# Motor.net
KiCad netlist of a schematic drawn in Altium Designer
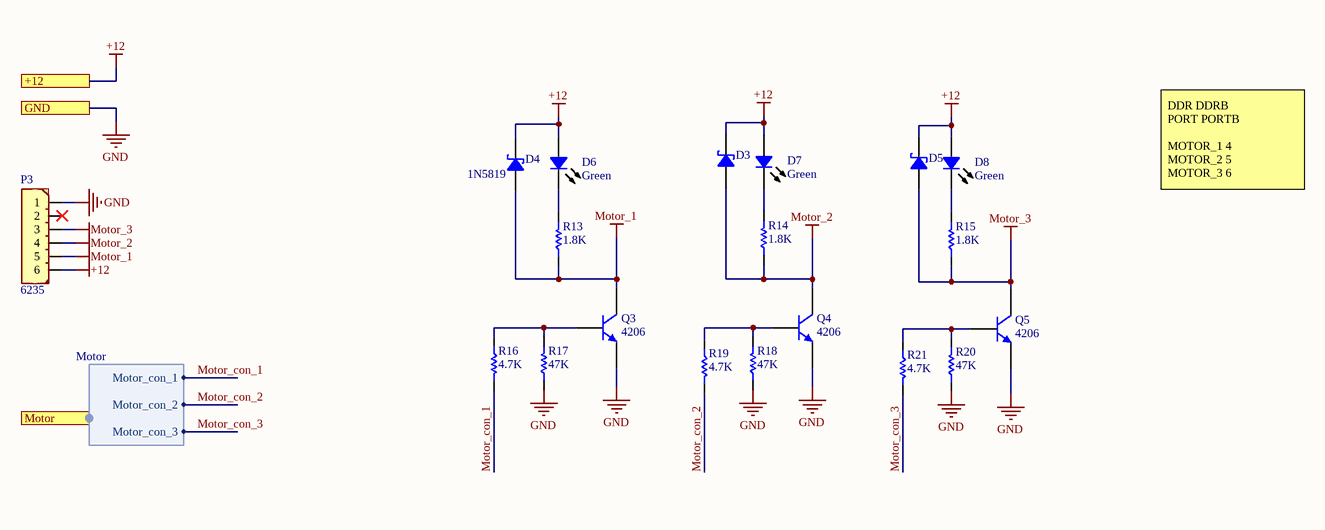
[diagram p0: Motor.SchDoc]

(export (version "E")
  (design (tool "Eeschema 10.0.6"))
  (components
    (comp (ref "D3")
      (value "1N5819")
      (footprint "430X270D")
      (description "Schottky Rectifiers")
      (fields (field (name "VALIDATION") "Valid"))
      (libsource (lib "aKaReZa") (part "Semi_Diod_Sch_1N5819_SMD"))
    )
    (comp (ref "D4")
      (value "1N5819")
      (footprint "430X270D")
      (description "Schottky Rectifiers")
      (fields (field (name "VALIDATION") "Valid"))
      (libsource (lib "aKaReZa") (part "Semi_Diod_Sch_1N5819_SMD"))
    )
    (comp (ref "D5")
      (value "1N5819")
      (footprint "430X270D")
      (description "Schottky Rectifiers")
      (fields (field (name "VALIDATION") "Valid"))
      (libsource (lib "aKaReZa") (part "Semi_Diod_Sch_1N5819_SMD"))
    )
    (comp (ref "D6")
      (value "Green")
      (footprint "LED 0805/2012 GREEN")
      (description "LED")
      (fields (field (name "VALIDATION") "Valid"))
      (libsource (lib "aKaReZa") (part "Semi_LED_SMD"))
    )
    (comp (ref "D7")
      (value "Green")
      (footprint "LED 0805/2012 GREEN")
      (description "LED")
      (fields (field (name "VALIDATION") "Valid"))
      (libsource (lib "aKaReZa") (part "Semi_LED_SMD"))
    )
    (comp (ref "D8")
      (value "Green")
      (footprint "LED 0805/2012 GREEN")
      (description "LED")
      (fields (field (name "VALIDATION") "Valid"))
      (libsource (lib "aKaReZa") (part "Semi_LED_SMD"))
    )
    (comp (ref "P3")
      (value "6'Pin")
      (footprint "645006114822")
      (description "6'Pin Power Connector")
      (fields (field (name "INFLOW") "6235") (field (name "VALIDATION") "Valid"))
      (libsource (lib "aKaReZa") (part "Con_Power_6_PC_V"))
    )
    (comp (ref "Q3")
      (value "NPN")
      (footprint "TO-220 AB")
      (description "NPN Power transistor")
      (fields (field (name "INFLOW") "4206") (field (name "VALIDATION") "NT"))
      (libsource (lib "aKaReZa") (part "Semi_BJT_TIP41C"))
    )
    (comp (ref "Q4")
      (value "NPN")
      (footprint "TO-220 AB")
      (description "NPN Power transistor")
      (fields (field (name "INFLOW") "4206") (field (name "VALIDATION") "NT"))
      (libsource (lib "aKaReZa") (part "Semi_BJT_TIP41C"))
    )
    (comp (ref "Q5")
      (value "NPN")
      (footprint "TO-220 AB")
      (description "NPN Power transistor")
      (fields (field (name "INFLOW") "4206") (field (name "VALIDATION") "NT"))
      (libsource (lib "aKaReZa") (part "Semi_BJT_TIP41C"))
    )
    (comp (ref "R13")
      (value "1.8K")
      (footprint "RES 0805 (2012X06L)")
      (description "Resistor")
      (fields (field (name "VALIDATION") "Valid"))
      (libsource (lib "aKaReZa") (part "Res_SMD_0805"))
    )
    (comp (ref "R14")
      (value "1.8K")
      (footprint "RES 0805 (2012X06L)")
      (description "Resistor")
      (fields (field (name "VALIDATION") "Valid"))
      (libsource (lib "aKaReZa") (part "Res_SMD_0805"))
    )
    (comp (ref "R15")
      (value "1.8K")
      (footprint "RES 0805 (2012X06L)")
      (description "Resistor")
      (fields (field (name "VALIDATION") "Valid"))
      (libsource (lib "aKaReZa") (part "Res_SMD_0805"))
    )
    (comp (ref "R16")
      (value "4.7K")
      (footprint "RES 1206 (3216X08L)")
      (description "Resistor")
      (fields (field (name "VALIDATION") "Valid"))
      (libsource (lib "aKaReZa") (part "Res_SMD_1206"))
    )
    (comp (ref "R17")
      (value "47K")
      (footprint "RES 1206 (3216X08L)")
      (description "Resistor")
      (fields (field (name "VALIDATION") "Valid"))
      (libsource (lib "aKaReZa") (part "Res_SMD_1206"))
    )
    (comp (ref "R18")
      (value "47K")
      (footprint "RES 1206 (3216X08L)")
      (description "Resistor")
      (fields (field (name "VALIDATION") "Valid"))
      (libsource (lib "aKaReZa") (part "Res_SMD_1206"))
    )
    (comp (ref "R19")
      (value "4.7K")
      (footprint "RES 1206 (3216X08L)")
      (description "Resistor")
      (fields (field (name "VALIDATION") "Valid"))
      (libsource (lib "aKaReZa") (part "Res_SMD_1206"))
    )
    (comp (ref "R20")
      (value "47K")
      (footprint "RES 1206 (3216X08L)")
      (description "Resistor")
      (fields (field (name "VALIDATION") "Valid"))
      (libsource (lib "aKaReZa") (part "Res_SMD_1206"))
    )
    (comp (ref "R21")
      (value "4.7K")
      (footprint "RES 1206 (3216X08L)")
      (description "Resistor")
      (fields (field (name "VALIDATION") "Valid"))
      (libsource (lib "aKaReZa") (part "Res_SMD_1206"))
    )
  )
  (nets
    (net (code "2") (name "+12") (class "Default")
      (node (ref "D3") (pin "2") (pinfunction "2_2") (pintype "passive"))
      (node (ref "D4") (pin "2") (pinfunction "2_2") (pintype "passive"))
      (node (ref "D5") (pin "2") (pinfunction "2_2") (pintype "passive"))
      (node (ref "D6") (pin "1") (pinfunction "1_1") (pintype "passive"))
      (node (ref "D7") (pin "1") (pinfunction "1_1") (pintype "passive"))
      (node (ref "D8") (pin "1") (pinfunction "1_1") (pintype "passive"))
      (node (ref "P3") (pin "6") (pinfunction "6_6") (pintype "passive"))
    )
    (net (code "4") (name "/Motor_con_1") (class "Default")
      (node (ref "R16") (pin "2") (pinfunction "2_2") (pintype "passive"))
    )
    (net (code "5") (name "/Motor_con_2") (class "Default")
      (node (ref "R19") (pin "2") (pinfunction "2_2") (pintype "passive"))
    )
    (net (code "6") (name "/Motor_con_3") (class "Default")
      (node (ref "R21") (pin "2") (pinfunction "2_2") (pintype "passive"))
    )
    (net (code "8") (name "GND") (class "Default")
      (node (ref "P3") (pin "1") (pinfunction "1_1") (pintype "passive"))
      (node (ref "Q3") (pin "3") (pinfunction "E_3") (pintype "passive"))
      (node (ref "Q4") (pin "3") (pinfunction "E_3") (pintype "passive"))
      (node (ref "Q5") (pin "3") (pinfunction "E_3") (pintype "passive"))
      (node (ref "R17") (pin "1") (pinfunction "1_1") (pintype "passive"))
      (node (ref "R18") (pin "1") (pinfunction "1_1") (pintype "passive"))
      (node (ref "R20") (pin "1") (pinfunction "1_1") (pintype "passive"))
    )
    (net (code "9") (name "Motor_1") (class "Default")
      (node (ref "D4") (pin "1") (pinfunction "1_1") (pintype "passive"))
      (node (ref "P3") (pin "5") (pinfunction "5_5") (pintype "passive"))
      (node (ref "Q3") (pin "2") (pinfunction "C_2") (pintype "passive"))
      (node (ref "R13") (pin "1") (pinfunction "1_1") (pintype "passive"))
    )
    (net (code "10") (name "Motor_2") (class "Default")
      (node (ref "D3") (pin "1") (pinfunction "1_1") (pintype "passive"))
      (node (ref "P3") (pin "4") (pinfunction "4_4") (pintype "passive"))
      (node (ref "Q4") (pin "2") (pinfunction "C_2") (pintype "passive"))
      (node (ref "R14") (pin "1") (pinfunction "1_1") (pintype "passive"))
    )
    (net (code "11") (name "Motor_3") (class "Default")
      (node (ref "D5") (pin "1") (pinfunction "1_1") (pintype "passive"))
      (node (ref "P3") (pin "3") (pinfunction "3_3") (pintype "passive"))
      (node (ref "Q5") (pin "2") (pinfunction "C_2") (pintype "passive"))
      (node (ref "R15") (pin "1") (pinfunction "1_1") (pintype "passive"))
    )
    (net (code "12") (name "Net-(D6-Pad2)") (class "Default")
      (node (ref "D6") (pin "2") (pinfunction "2_2") (pintype "passive"))
      (node (ref "R13") (pin "2") (pinfunction "2_2") (pintype "passive"))
    )
    (net (code "13") (name "Net-(D7-Pad2)") (class "Default")
      (node (ref "D7") (pin "2") (pinfunction "2_2") (pintype "passive"))
      (node (ref "R14") (pin "2") (pinfunction "2_2") (pintype "passive"))
    )
    (net (code "14") (name "Net-(D8-Pad2)") (class "Default")
      (node (ref "D8") (pin "2") (pinfunction "2_2") (pintype "passive"))
      (node (ref "R15") (pin "2") (pinfunction "2_2") (pintype "passive"))
    )
    (net (code "15") (name "Net-(Q3-B)") (class "Default")
      (node (ref "Q3") (pin "1") (pinfunction "B_1") (pintype "passive"))
      (node (ref "R16") (pin "1") (pinfunction "1_1") (pintype "passive"))
      (node (ref "R17") (pin "2") (pinfunction "2_2") (pintype "passive"))
    )
    (net (code "16") (name "Net-(Q4-B)") (class "Default")
      (node (ref "Q4") (pin "1") (pinfunction "B_1") (pintype "passive"))
      (node (ref "R18") (pin "2") (pinfunction "2_2") (pintype "passive"))
      (node (ref "R19") (pin "1") (pinfunction "1_1") (pintype "passive"))
    )
    (net (code "17") (name "Net-(Q5-B)") (class "Default")
      (node (ref "Q5") (pin "1") (pinfunction "B_1") (pintype "passive"))
      (node (ref "R20") (pin "2") (pinfunction "2_2") (pintype "passive"))
      (node (ref "R21") (pin "1") (pinfunction "1_1") (pintype "passive"))
    )
    (net (code "18") (name "unconnected-(P3-Pad2)") (class "Default")
      (node (ref "P3") (pin "2") (pinfunction "2_2") (pintype "passive+no_connect"))
    )
  )
)
